# power_supplies.net
KiCad netlist of a schematic drawn in Altium Designer
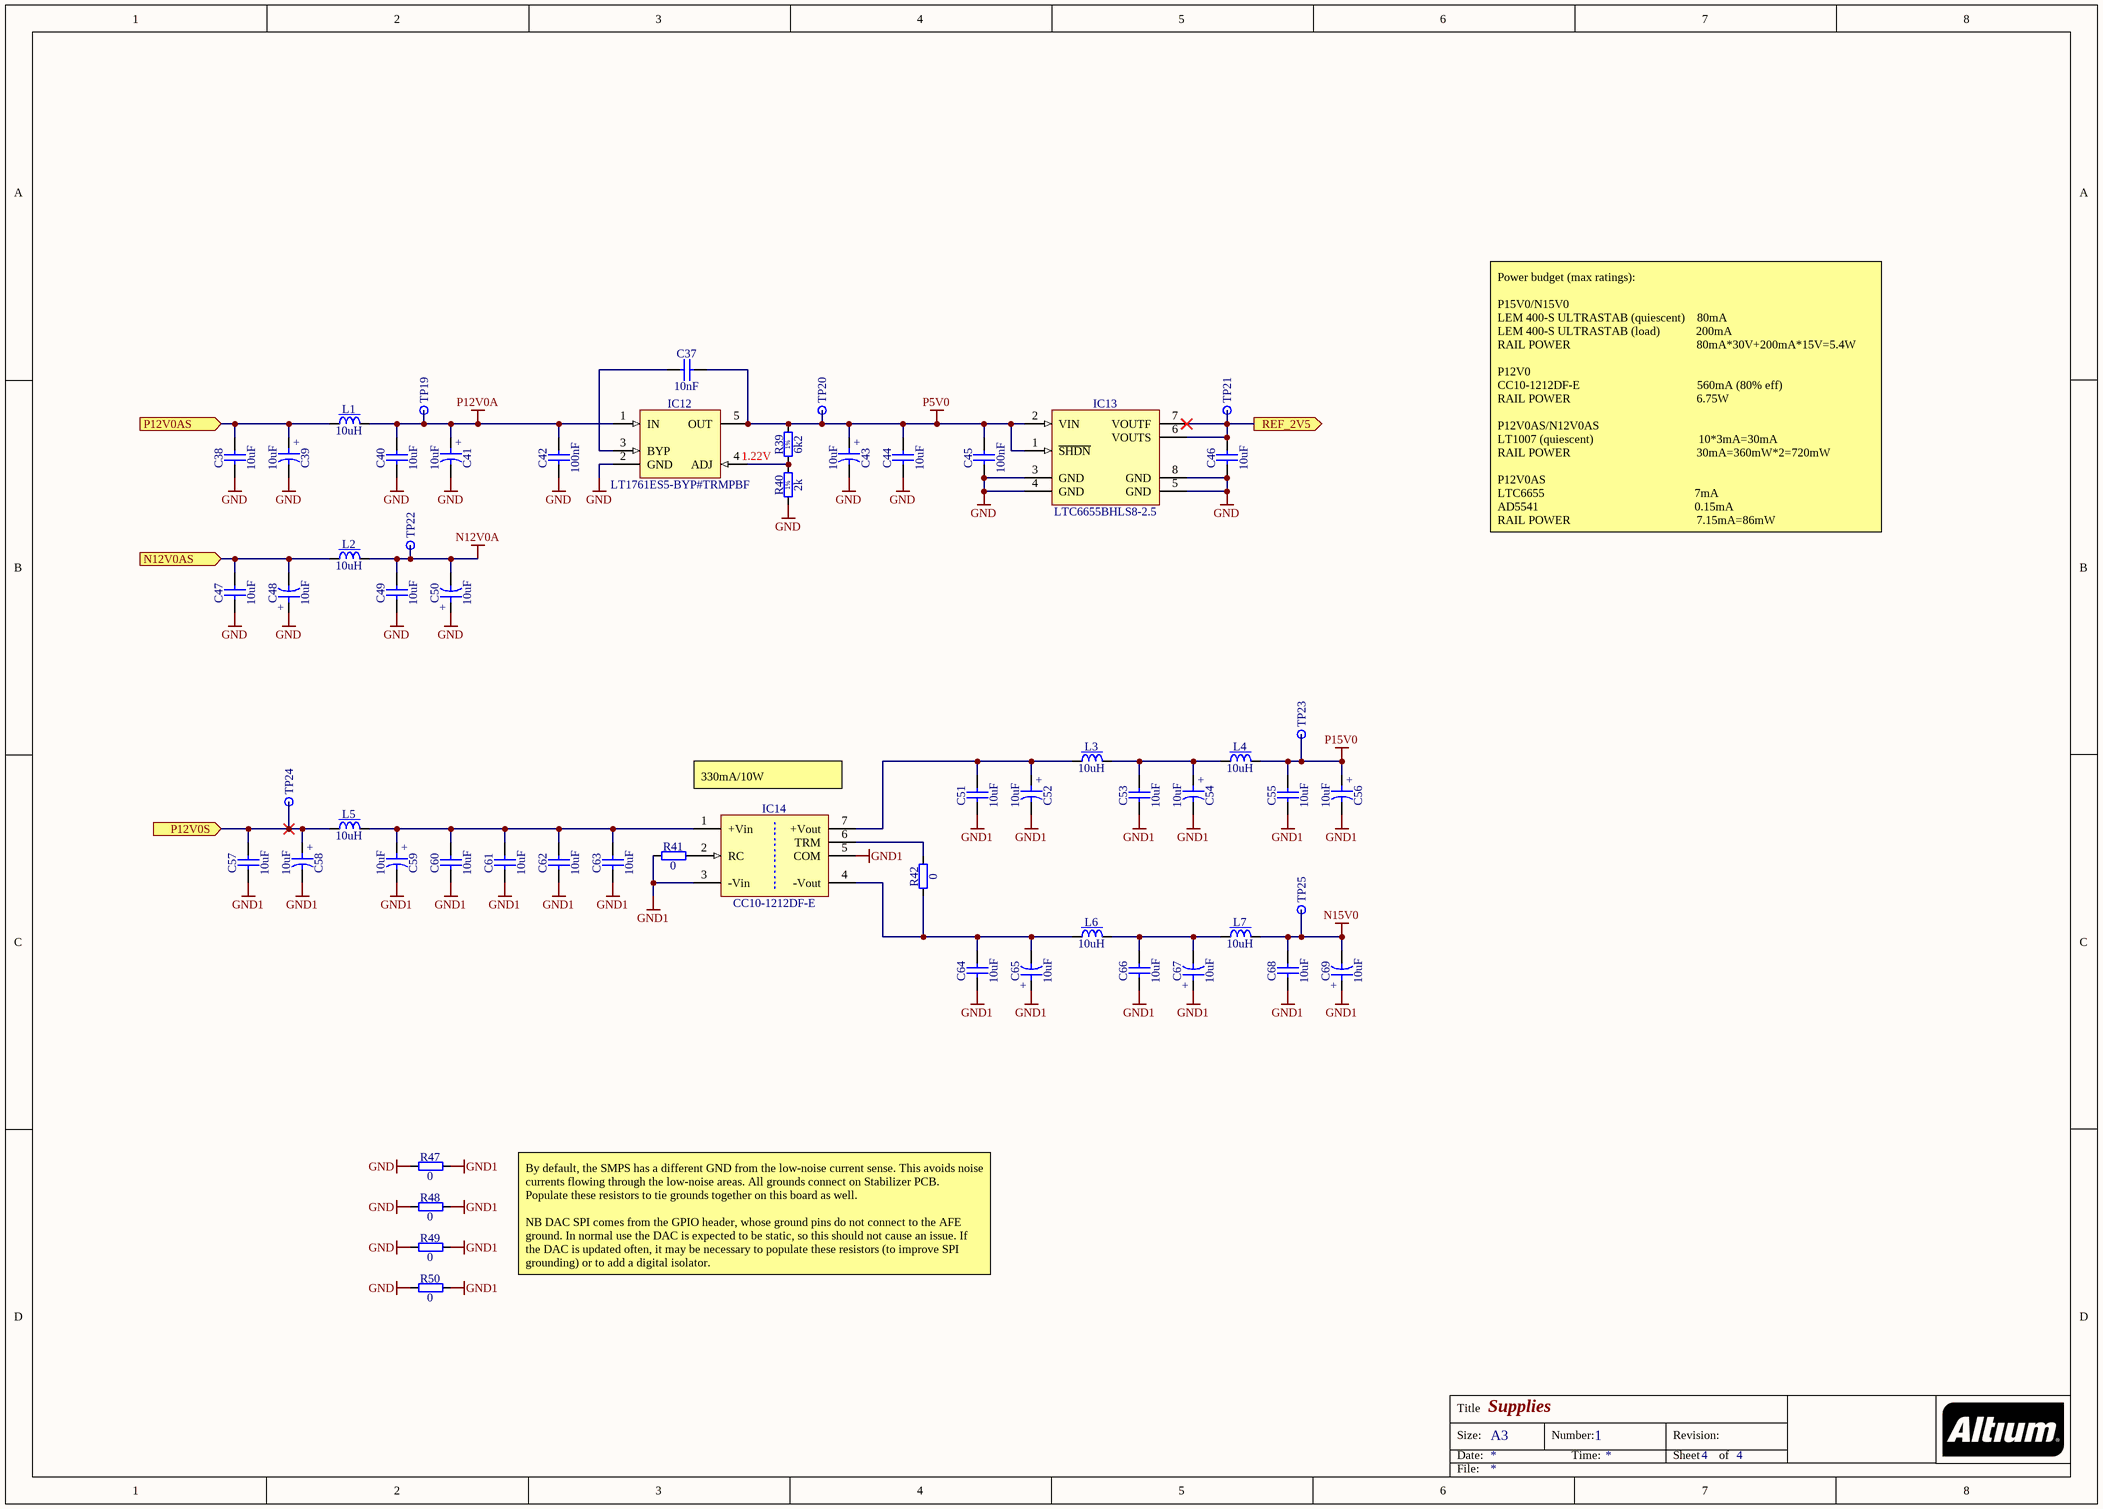
[diagram p0: power_supplies.SchDoc]

(export (version "E")
  (design (tool "Eeschema 10.0.6"))
  (components
    (comp (ref "C37")
      (value "10nF")
      (footprint "CAPC1608X87N")
      (description "Non-polarised capacitor")
      (fields
        (field (name "PART NUMBER") "CC0603_10NF_50V_10%_X7R")
        (field (name "VOLTAGE") "50V")
        (field (name "AUTHOR") "CERN DEM JLC")
      )
      (libsource (lib "Capacitors") (part "Capacitor - non polarized"))
    )
    (comp (ref "C38")
      (value "10uF")
      (footprint "CAPC2012X95N")
      (description "Non-polarised capacitor")
      (fields
        (field (name "PART NUMBER") "CC0805_10UF_25V_10%_X5R")
        (field (name "VOLTAGE") "25V")
        (field (name "AUTHOR") "CERN DEM JLC")
      )
      (libsource (lib "Capacitors") (part "Capacitor - non polarized"))
    )
    (comp (ref "C39")
      (value "10uF")
      (footprint "CAPMP6032X280N")
      (description "Polarised capacitor")
      (fields
        (field (name "PART NUMBER") "CTE6032-28_10UF_25V_10%_LESR0500")
        (field (name "VOLTAGE") "25V")
        (field (name "AUTHOR") "CERN DEM JLC")
      )
      (libsource (lib "Capacitors") (part "Capacitor - polarized"))
    )
    (comp (ref "C40")
      (value "10uF")
      (footprint "CAPC2012X95N")
      (description "Non-polarised capacitor")
      (fields
        (field (name "PART NUMBER") "CC0805_10UF_25V_10%_X5R")
        (field (name "VOLTAGE") "25V")
        (field (name "AUTHOR") "CERN DEM JLC")
      )
      (libsource (lib "Capacitors") (part "Capacitor - non polarized"))
    )
    (comp (ref "C41")
      (value "10uF")
      (footprint "CAPMP6032X280N")
      (description "Polarised capacitor")
      (fields
        (field (name "PART NUMBER") "CTE6032-28_10UF_25V_10%_LESR0500")
        (field (name "VOLTAGE") "25V")
        (field (name "AUTHOR") "CERN DEM JLC")
      )
      (libsource (lib "Capacitors") (part "Capacitor - polarized"))
    )
    (comp (ref "C42")
      (value "100nF")
      (footprint "CAPC1608X87N")
      (description "Non-polarised capacitor")
      (fields
        (field (name "PART NUMBER") "CC0603_100NF_50V_10%_X7R")
        (field (name "VOLTAGE") "50V")
        (field (name "AUTHOR") "CERN DEM JLC")
      )
      (libsource (lib "Capacitors") (part "Capacitor - non polarized"))
    )
    (comp (ref "C43")
      (value "10uF")
      (footprint "CAPMP6032X280N")
      (description "Polarised capacitor")
      (fields
        (field (name "PART NUMBER") "CTE6032-28_10UF_25V_10%_LESR0500")
        (field (name "VOLTAGE") "25V")
        (field (name "AUTHOR") "CERN DEM JLC")
      )
      (libsource (lib "Capacitors") (part "Capacitor - polarized"))
    )
    (comp (ref "C44")
      (value "10uF")
      (footprint "CAPC2012X95N")
      (description "Non-polarised capacitor")
      (fields
        (field (name "PART NUMBER") "CC0805_10UF_25V_10%_X5R")
        (field (name "VOLTAGE") "25V")
        (field (name "AUTHOR") "CERN DEM JLC")
      )
      (libsource (lib "Capacitors") (part "Capacitor - non polarized"))
    )
    (comp (ref "C45")
      (value "100nF")
      (footprint "CAPC1608X87N")
      (description "Non-polarised capacitor")
      (fields
        (field (name "PART NUMBER") "CC0603_100NF_50V_10%_X7R")
        (field (name "VOLTAGE") "50V")
        (field (name "AUTHOR") "CERN DEM JLC")
      )
      (libsource (lib "Capacitors") (part "Capacitor - non polarized"))
    )
    (comp (ref "C46")
      (value "10uF")
      (footprint "CAPC2012X95N")
      (description "Non-polarised capacitor")
      (fields
        (field (name "PART NUMBER") "CC0805_10UF_25V_10%_X5R")
        (field (name "VOLTAGE") "25V")
        (field (name "AUTHOR") "CERN DEM JLC")
      )
      (libsource (lib "Capacitors") (part "Capacitor - non polarized"))
    )
    (comp (ref "C47")
      (value "10uF")
      (footprint "CAPC2012X95N")
      (description "Non-polarised capacitor")
      (fields
        (field (name "PART NUMBER") "CC0805_10UF_25V_10%_X5R")
        (field (name "VOLTAGE") "25V")
        (field (name "AUTHOR") "CERN DEM JLC")
      )
      (libsource (lib "Capacitors") (part "Capacitor - non polarized"))
    )
    (comp (ref "C48")
      (value "10uF")
      (footprint "CAPMP6032X280N")
      (description "Polarised capacitor")
      (fields
        (field (name "PART NUMBER") "CTE6032-28_10UF_25V_10%_LESR0500")
        (field (name "VOLTAGE") "25V")
        (field (name "AUTHOR") "CERN DEM JLC")
      )
      (libsource (lib "Capacitors") (part "Capacitor - polarized"))
    )
    (comp (ref "C49")
      (value "10uF")
      (footprint "CAPC2012X95N")
      (description "Non-polarised capacitor")
      (fields
        (field (name "PART NUMBER") "CC0805_10UF_25V_10%_X5R")
        (field (name "VOLTAGE") "25V")
        (field (name "AUTHOR") "CERN DEM JLC")
      )
      (libsource (lib "Capacitors") (part "Capacitor - non polarized"))
    )
    (comp (ref "C50")
      (value "10uF")
      (footprint "CAPMP6032X280N")
      (description "Polarised capacitor")
      (fields
        (field (name "PART NUMBER") "CTE6032-28_10UF_25V_10%_LESR0500")
        (field (name "VOLTAGE") "25V")
        (field (name "AUTHOR") "CERN DEM JLC")
      )
      (libsource (lib "Capacitors") (part "Capacitor - polarized"))
    )
    (comp (ref "C51")
      (value "10uF")
      (footprint "CAPC2012X95N")
      (description "Non-polarised capacitor")
      (fields
        (field (name "PART NUMBER") "CC0805_10UF_25V_10%_X5R")
        (field (name "VOLTAGE") "25V")
        (field (name "AUTHOR") "CERN DEM JLC")
      )
      (libsource (lib "Capacitors") (part "Capacitor - non polarized"))
    )
    (comp (ref "C52")
      (value "10uF")
      (footprint "CAPMP6032X280N")
      (description "Polarised capacitor")
      (fields
        (field (name "PART NUMBER") "CTE6032-28_10UF_25V_10%_LESR0500")
        (field (name "VOLTAGE") "25V")
        (field (name "AUTHOR") "CERN DEM JLC")
      )
      (libsource (lib "Capacitors") (part "Capacitor - polarized"))
    )
    (comp (ref "C53")
      (value "10uF")
      (footprint "CAPC2012X95N")
      (description "Non-polarised capacitor")
      (fields
        (field (name "PART NUMBER") "CC0805_10UF_25V_10%_X5R")
        (field (name "VOLTAGE") "25V")
        (field (name "AUTHOR") "CERN DEM JLC")
      )
      (libsource (lib "Capacitors") (part "Capacitor - non polarized"))
    )
    (comp (ref "C54")
      (value "10uF")
      (footprint "CAPMP6032X280N")
      (description "Polarised capacitor")
      (fields
        (field (name "PART NUMBER") "CTE6032-28_10UF_25V_10%_LESR0500")
        (field (name "VOLTAGE") "25V")
        (field (name "AUTHOR") "CERN DEM JLC")
      )
      (libsource (lib "Capacitors") (part "Capacitor - polarized"))
    )
    (comp (ref "C55")
      (value "10uF")
      (footprint "CAPC2012X95N")
      (description "Non-polarised capacitor")
      (fields
        (field (name "PART NUMBER") "CC0805_10UF_25V_10%_X5R")
        (field (name "VOLTAGE") "25V")
        (field (name "AUTHOR") "CERN DEM JLC")
      )
      (libsource (lib "Capacitors") (part "Capacitor - non polarized"))
    )
    (comp (ref "C56")
      (value "10uF")
      (footprint "CAPMP6032X280N")
      (description "Polarised capacitor")
      (fields
        (field (name "PART NUMBER") "CTE6032-28_10UF_25V_10%_LESR0500")
        (field (name "VOLTAGE") "25V")
        (field (name "AUTHOR") "CERN DEM JLC")
      )
      (libsource (lib "Capacitors") (part "Capacitor - polarized"))
    )
    (comp (ref "C57")
      (value "10uF")
      (footprint "CAPC2012X95N")
      (description "Non-polarised capacitor")
      (fields
        (field (name "PART NUMBER") "CC0805_10UF_25V_10%_X5R")
        (field (name "VOLTAGE") "25V")
        (field (name "AUTHOR") "CERN DEM JLC")
      )
      (libsource (lib "Capacitors") (part "Capacitor - non polarized"))
    )
    (comp (ref "C58")
      (value "10uF")
      (footprint "CAPMP6032X280N")
      (description "Polarised capacitor")
      (fields
        (field (name "PART NUMBER") "CTE6032-28_10UF_25V_10%_LESR0500")
        (field (name "VOLTAGE") "25V")
        (field (name "AUTHOR") "CERN DEM JLC")
      )
      (libsource (lib "Capacitors") (part "Capacitor - polarized"))
    )
    (comp (ref "C59")
      (value "10uF")
      (footprint "CAPMP6032X280N")
      (description "Polarised capacitor")
      (fields
        (field (name "PART NUMBER") "CTE6032-28_10UF_25V_10%_LESR0500")
        (field (name "VOLTAGE") "25V")
        (field (name "AUTHOR") "CERN DEM JLC")
      )
      (libsource (lib "Capacitors") (part "Capacitor - polarized"))
    )
    (comp (ref "C60")
      (value "10uF")
      (footprint "CAPC2012X95N")
      (description "Non-polarised capacitor")
      (fields
        (field (name "PART NUMBER") "CC0805_10UF_25V_10%_X5R")
        (field (name "VOLTAGE") "25V")
        (field (name "AUTHOR") "CERN DEM JLC")
      )
      (libsource (lib "Capacitors") (part "Capacitor - non polarized"))
    )
    (comp (ref "C61")
      (value "10uF")
      (footprint "CAPC2012X95N")
      (description "Non-polarised capacitor")
      (fields
        (field (name "PART NUMBER") "CC0805_10UF_25V_10%_X5R")
        (field (name "VOLTAGE") "25V")
        (field (name "AUTHOR") "CERN DEM JLC")
      )
      (libsource (lib "Capacitors") (part "Capacitor - non polarized"))
    )
    (comp (ref "C62")
      (value "10uF")
      (footprint "CAPC2012X95N")
      (description "Non-polarised capacitor")
      (fields
        (field (name "PART NUMBER") "CC0805_10UF_25V_10%_X5R")
        (field (name "VOLTAGE") "25V")
        (field (name "AUTHOR") "CERN DEM JLC")
      )
      (libsource (lib "Capacitors") (part "Capacitor - non polarized"))
    )
    (comp (ref "C63")
      (value "10uF")
      (footprint "CAPC2012X95N")
      (description "Non-polarised capacitor")
      (fields
        (field (name "PART NUMBER") "CC0805_10UF_25V_10%_X5R")
        (field (name "VOLTAGE") "25V")
        (field (name "AUTHOR") "CERN DEM JLC")
      )
      (libsource (lib "Capacitors") (part "Capacitor - non polarized"))
    )
    (comp (ref "C64")
      (value "10uF")
      (footprint "CAPC2012X95N")
      (description "Non-polarised capacitor")
      (fields
        (field (name "PART NUMBER") "CC0805_10UF_25V_10%_X5R")
        (field (name "VOLTAGE") "25V")
        (field (name "AUTHOR") "CERN DEM JLC")
      )
      (libsource (lib "Capacitors") (part "Capacitor - non polarized"))
    )
    (comp (ref "C65")
      (value "10uF")
      (footprint "CAPMP6032X280N")
      (description "Polarised capacitor")
      (fields
        (field (name "PART NUMBER") "CTE6032-28_10UF_25V_10%_LESR0500")
        (field (name "VOLTAGE") "25V")
        (field (name "AUTHOR") "CERN DEM JLC")
      )
      (libsource (lib "Capacitors") (part "Capacitor - polarized"))
    )
    (comp (ref "C66")
      (value "10uF")
      (footprint "CAPC2012X95N")
      (description "Non-polarised capacitor")
      (fields
        (field (name "PART NUMBER") "CC0805_10UF_25V_10%_X5R")
        (field (name "VOLTAGE") "25V")
        (field (name "AUTHOR") "CERN DEM JLC")
      )
      (libsource (lib "Capacitors") (part "Capacitor - non polarized"))
    )
    (comp (ref "C67")
      (value "10uF")
      (footprint "CAPMP6032X280N")
      (description "Polarised capacitor")
      (fields
        (field (name "PART NUMBER") "CTE6032-28_10UF_25V_10%_LESR0500")
        (field (name "VOLTAGE") "25V")
        (field (name "AUTHOR") "CERN DEM JLC")
      )
      (libsource (lib "Capacitors") (part "Capacitor - polarized"))
    )
    (comp (ref "C68")
      (value "10uF")
      (footprint "CAPC2012X95N")
      (description "Non-polarised capacitor")
      (fields
        (field (name "PART NUMBER") "CC0805_10UF_25V_10%_X5R")
        (field (name "VOLTAGE") "25V")
        (field (name "AUTHOR") "CERN DEM JLC")
      )
      (libsource (lib "Capacitors") (part "Capacitor - non polarized"))
    )
    (comp (ref "C69")
      (value "10uF")
      (footprint "CAPMP6032X280N")
      (description "Polarised capacitor")
      (fields
        (field (name "PART NUMBER") "CTE6032-28_10UF_25V_10%_LESR0500")
        (field (name "VOLTAGE") "25V")
        (field (name "AUTHOR") "CERN DEM JLC")
      )
      (libsource (lib "Capacitors") (part "Capacitor - polarized"))
    )
    (comp (ref "IC12")
      (value "LT1761ES5-BYP#TRMPBF")
      (footprint "SOT95P280X100-5N")
      (description "100mA, Low Noise, LDO Micropower Adjustable Regulator in SOT-23")
      (fields (field (name "MANUFACTURER") "LINEAR TECHNOLOGY") (field (name "AUTHOR") "CERN DEM MR"))
      (libsource (lib "ICs And Semiconductors") (part "LT1761-BYP"))
    )
    (comp (ref "IC13")
      (value "LTC6655BHLS8-2.5")
      (footprint "LT_LS8")
      (description "2.5V, 0.25ppm Noise, Low Drift Precision Buffered Voltage Reference")
      (fields
        (field (name "MANUFACTURER") "ANALOG DEVICES")
        (field (name "MANUFACTURER PART NUMBER") "LTC6655BHLS8-2.5#PBF")
      )
      (libsource (lib "ICs") (part "LTC6655BHLS8-2.5#PBF"))
    )
    (comp (ref "IC14")
      (value "CC10-1212DF-E")
      (footprint "library-modules:CC10-1212DF-E")
      (description "CONV DC/DC 10W DUAL 12V +-12V PCB")
      (fields (field (name "MANUFACTURER") "TDK-Lambda Americas Inc.") (field (name "AUTHOR") "TPH"))
      (libsource (lib "LIBRARY_SCH") (part "DC/DC_CC10-1212DF-E"))
    )
    (comp (ref "L1")
      (value "10uH")
      (footprint "IND_MURATA-PS_8400")
      (description "Inductor With Core")
      (fields
        (field (name "PART NUMBER") "IND_10UH_10%_MURATA-PS_8400")
        (field (name "POWER") "950mA")
        (field (name "AUTHOR") "CERN DEM JLC")
      )
      (libsource (lib "Inductors & Transformers") (part "Inductor With Magnetic core"))
    )
    (comp (ref "L2")
      (value "10uH")
      (footprint "IND_MURATA-PS_8400")
      (description "Inductor With Core")
      (fields
        (field (name "PART NUMBER") "IND_10UH_10%_MURATA-PS_8400")
        (field (name "POWER") "950mA")
        (field (name "AUTHOR") "CERN DEM JLC")
      )
      (libsource (lib "Inductors & Transformers") (part "Inductor With Magnetic core"))
    )
    (comp (ref "L3")
      (value "10uH")
      (footprint "IND_MURATA-PS_8400")
      (description "Inductor With Core")
      (fields
        (field (name "PART NUMBER") "IND_10UH_10%_MURATA-PS_8400")
        (field (name "POWER") "950mA")
        (field (name "AUTHOR") "CERN DEM JLC")
      )
      (libsource (lib "Inductors & Transformers") (part "Inductor With Magnetic core"))
    )
    (comp (ref "L4")
      (value "10uH")
      (footprint "IND_MURATA-PS_8400")
      (description "Inductor With Core")
      (fields
        (field (name "PART NUMBER") "IND_10UH_10%_MURATA-PS_8400")
        (field (name "POWER") "950mA")
        (field (name "AUTHOR") "CERN DEM JLC")
      )
      (libsource (lib "Inductors & Transformers") (part "Inductor With Magnetic core"))
    )
    (comp (ref "L5")
      (value "10uH")
      (footprint "IND_MURATA-PS_8400")
      (description "Inductor With Core")
      (fields
        (field (name "PART NUMBER") "IND_10UH_10%_MURATA-PS_8400")
        (field (name "POWER") "950mA")
        (field (name "AUTHOR") "CERN DEM JLC")
      )
      (libsource (lib "Inductors & Transformers") (part "Inductor With Magnetic core"))
    )
    (comp (ref "L6")
      (value "10uH")
      (footprint "IND_MURATA-PS_8400")
      (description "Inductor With Core")
      (fields
        (field (name "PART NUMBER") "IND_10UH_10%_MURATA-PS_8400")
        (field (name "POWER") "950mA")
        (field (name "AUTHOR") "CERN DEM JLC")
      )
      (libsource (lib "Inductors & Transformers") (part "Inductor With Magnetic core"))
    )
    (comp (ref "L7")
      (value "10uH")
      (footprint "IND_MURATA-PS_8400")
      (description "Inductor With Core")
      (fields
        (field (name "PART NUMBER") "IND_10UH_10%_MURATA-PS_8400")
        (field (name "POWER") "950mA")
        (field (name "AUTHOR") "CERN DEM JLC")
      )
      (libsource (lib "Inductors & Transformers") (part "Inductor With Magnetic core"))
    )
    (comp (ref "R39")
      (value "6k2")
      (footprint "RESC1608X55N")
      (description "Resistor - 1%")
      (fields
        (field (name "PART NUMBER") "R0603_6K2_1%_0.1W_100PPM")
        (field (name "POWER") "0.1W")
        (field (name "AUTHOR") "CERN DEM JLC")
      )
      (libsource (lib "Resistors") (part "Resistor - 1%"))
    )
    (comp (ref "R40")
      (value "2k")
      (footprint "RESC1608X55N")
      (description "Resistor - 1%")
      (fields
        (field (name "PART NUMBER") "R0603_2K_1%_0.1W_100PPM")
        (field (name "POWER") "0.1W")
        (field (name "AUTHOR") "CERN DEM JLC")
      )
      (libsource (lib "Resistors") (part "Resistor - 1%"))
    )
    (comp (ref "R41")
      (value "0")
      (footprint "RESC1608X55N")
      (description "Resistor")
      (fields
        (field (name "PART NUMBER") "R0603_0R_JUMPER")
        (field (name "MANUFACTURER") "GENERIC")
        (field (name "AUTHOR") "CERN DEM JLC")
      )
      (libsource (lib "Resistors") (part "Resistor"))
    )
    (comp (ref "R42")
      (value "0")
      (footprint "RESC1608X55N")
      (description "Resistor")
      (fields
        (field (name "PART NUMBER") "R0603_0R_JUMPER")
        (field (name "MANUFACTURER") "GENERIC")
        (field (name "AUTHOR") "CERN DEM JLC")
      )
      (libsource (lib "Resistors") (part "Resistor"))
    )
    (comp (ref "R47")
      (value "0")
      (footprint "RESC1608X55N")
      (description "Resistor")
      (fields
        (field (name "PART NUMBER") "R0603_0R_JUMPER")
        (field (name "MANUFACTURER") "GENERIC")
        (field (name "AUTHOR") "CERN DEM JLC")
      )
      (libsource (lib "Resistors") (part "Resistor"))
    )
    (comp (ref "R48")
      (value "0")
      (footprint "RESC1608X55N")
      (description "Resistor")
      (fields
        (field (name "PART NUMBER") "R0603_0R_JUMPER")
        (field (name "MANUFACTURER") "GENERIC")
        (field (name "AUTHOR") "CERN DEM JLC")
      )
      (libsource (lib "Resistors") (part "Resistor"))
    )
    (comp (ref "R49")
      (value "0")
      (footprint "RESC1608X55N")
      (description "Resistor")
      (fields
        (field (name "PART NUMBER") "R0603_0R_JUMPER")
        (field (name "MANUFACTURER") "GENERIC")
        (field (name "AUTHOR") "CERN DEM JLC")
      )
      (libsource (lib "Resistors") (part "Resistor"))
    )
    (comp (ref "R50")
      (value "0")
      (footprint "RESC1608X55N")
      (description "Resistor")
      (fields
        (field (name "PART NUMBER") "R0603_0R_JUMPER")
        (field (name "MANUFACTURER") "GENERIC")
        (field (name "AUTHOR") "CERN DEM JLC")
      )
      (libsource (lib "Resistors") (part "Resistor"))
    )
    (comp (ref "TP19")
      (value "Test Point")
      (footprint "TPS127")
      (fields (field (name "PART NUMBER") "SMD_PAD_1.27X1.27MM") (field (name "AUTHOR") "CERN DEM JLC"))
      (libsource (lib "Eletro-mechanical") (part "Test Point"))
    )
    (comp (ref "TP20")
      (value "Test Point")
      (footprint "TPS127")
      (fields (field (name "PART NUMBER") "SMD_PAD_1.27X1.27MM") (field (name "AUTHOR") "CERN DEM JLC"))
      (libsource (lib "Eletro-mechanical") (part "Test Point"))
    )
    (comp (ref "TP21")
      (value "Test Point")
      (footprint "TPS127")
      (fields (field (name "PART NUMBER") "SMD_PAD_1.27X1.27MM") (field (name "AUTHOR") "CERN DEM JLC"))
      (libsource (lib "Eletro-mechanical") (part "Test Point"))
    )
    (comp (ref "TP22")
      (value "Test Point")
      (footprint "TPS127")
      (fields (field (name "PART NUMBER") "SMD_PAD_1.27X1.27MM") (field (name "AUTHOR") "CERN DEM JLC"))
      (libsource (lib "Eletro-mechanical") (part "Test Point"))
    )
    (comp (ref "TP23")
      (value "Test Point")
      (footprint "TPS127")
      (fields (field (name "PART NUMBER") "SMD_PAD_1.27X1.27MM") (field (name "AUTHOR") "CERN DEM JLC"))
      (libsource (lib "Eletro-mechanical") (part "Test Point"))
    )
    (comp (ref "TP24")
      (value "Test Point")
      (footprint "TPS127")
      (fields (field (name "PART NUMBER") "SMD_PAD_1.27X1.27MM") (field (name "AUTHOR") "CERN DEM JLC"))
      (libsource (lib "Eletro-mechanical") (part "Test Point"))
    )
    (comp (ref "TP25")
      (value "Test Point")
      (footprint "TPS127")
      (fields (field (name "PART NUMBER") "SMD_PAD_1.27X1.27MM") (field (name "AUTHOR") "CERN DEM JLC"))
      (libsource (lib "Eletro-mechanical") (part "Test Point"))
    )
  )
  (nets
    (net (code "1") (name "/N12V0AS") (class "Default")
      (node (ref "C47") (pin "2") (pinfunction "2_2") (pintype "passive"))
      (node (ref "C48") (pin "2") (pinfunction "2_2") (pintype "passive"))
      (node (ref "L2") (pin "1") (pinfunction "1_1") (pintype "passive"))
    )
    (net (code "2") (name "/P12V0AS") (class "Default")
      (node (ref "C38") (pin "2") (pinfunction "2_2") (pintype "passive"))
      (node (ref "C39") (pin "1") (pinfunction "1_1") (pintype "passive"))
      (node (ref "L1") (pin "1") (pinfunction "1_1") (pintype "passive"))
    )
    (net (code "3") (name "/P12V0S") (class "Default")
      (node (ref "C57") (pin "2") (pinfunction "2_2") (pintype "passive"))
      (node (ref "C58") (pin "1") (pinfunction "1_1") (pintype "passive"))
      (node (ref "L5") (pin "1") (pinfunction "1_1") (pintype "passive"))
      (node (ref "TP24") (pin "1") (pinfunction "1_1") (pintype "bidirectional"))
    )
    (net (code "4") (name "/REF_2V5") (class "Default")
      (node (ref "C46") (pin "2") (pinfunction "2_2") (pintype "passive"))
      (node (ref "IC13") (pin "6") (pinfunction "VOUTS_6") (pintype "power_in"))
      (node (ref "IC13") (pin "7") (pinfunction "VOUTF_7") (pintype "power_in"))
      (node (ref "TP21") (pin "1") (pinfunction "1_1") (pintype "bidirectional"))
    )
    (net (code "5") (name "GND") (class "Default")
      (node (ref "C38") (pin "1") (pinfunction "1_1") (pintype "passive"))
      (node (ref "C39") (pin "2") (pinfunction "2_2") (pintype "passive"))
      (node (ref "C40") (pin "1") (pinfunction "1_1") (pintype "passive"))
      (node (ref "C41") (pin "2") (pinfunction "2_2") (pintype "passive"))
      (node (ref "C42") (pin "1") (pinfunction "1_1") (pintype "passive"))
      (node (ref "C43") (pin "2") (pinfunction "2_2") (pintype "passive"))
      (node (ref "C44") (pin "1") (pinfunction "1_1") (pintype "passive"))
      (node (ref "C45") (pin "1") (pinfunction "1_1") (pintype "passive"))
      (node (ref "C46") (pin "1") (pinfunction "1_1") (pintype "passive"))
      (node (ref "C47") (pin "1") (pinfunction "1_1") (pintype "passive"))
      (node (ref "C48") (pin "1") (pinfunction "1_1") (pintype "passive"))
      (node (ref "C49") (pin "1") (pinfunction "1_1") (pintype "passive"))
      (node (ref "C50") (pin "1") (pinfunction "1_1") (pintype "passive"))
      (node (ref "IC12") (pin "2") (pinfunction "GND_2") (pintype "power_in"))
      (node (ref "IC13") (pin "3") (pinfunction "GND_3") (pintype "power_in"))
      (node (ref "IC13") (pin "4") (pinfunction "GND_4") (pintype "power_in"))
      (node (ref "IC13") (pin "5") (pinfunction "GND_5") (pintype "power_in"))
      (node (ref "IC13") (pin "8") (pinfunction "GND_8") (pintype "power_in"))
      (node (ref "R40") (pin "1") (pinfunction "1_1") (pintype "passive"))
      (node (ref "R47") (pin "1") (pinfunction "1_1") (pintype "passive"))
      (node (ref "R48") (pin "1") (pinfunction "1_1") (pintype "passive"))
      (node (ref "R49") (pin "1") (pinfunction "1_1") (pintype "passive"))
      (node (ref "R50") (pin "1") (pinfunction "1_1") (pintype "passive"))
    )
    (net (code "6") (name "GND1") (class "Default")
      (node (ref "C51") (pin "1") (pinfunction "1_1") (pintype "passive"))
      (node (ref "C52") (pin "2") (pinfunction "2_2") (pintype "passive"))
      (node (ref "C53") (pin "1") (pinfunction "1_1") (pintype "passive"))
      (node (ref "C54") (pin "2") (pinfunction "2_2") (pintype "passive"))
      (node (ref "C55") (pin "1") (pinfunction "1_1") (pintype "passive"))
      (node (ref "C56") (pin "2") (pinfunction "2_2") (pintype "passive"))
      (node (ref "C57") (pin "1") (pinfunction "1_1") (pintype "passive"))
      (node (ref "C58") (pin "2") (pinfunction "2_2") (pintype "passive"))
      (node (ref "C59") (pin "2") (pinfunction "2_2") (pintype "passive"))
      (node (ref "C60") (pin "1") (pinfunction "1_1") (pintype "passive"))
      (node (ref "C61") (pin "1") (pinfunction "1_1") (pintype "passive"))
      (node (ref "C62") (pin "1") (pinfunction "1_1") (pintype "passive"))
      (node (ref "C63") (pin "1") (pinfunction "1_1") (pintype "passive"))
      (node (ref "C64") (pin "1") (pinfunction "1_1") (pintype "passive"))
      (node (ref "C65") (pin "1") (pinfunction "1_1") (pintype "passive"))
      (node (ref "C66") (pin "1") (pinfunction "1_1") (pintype "passive"))
      (node (ref "C67") (pin "1") (pinfunction "1_1") (pintype "passive"))
      (node (ref "C68") (pin "1") (pinfunction "1_1") (pintype "passive"))
      (node (ref "C69") (pin "1") (pinfunction "1_1") (pintype "passive"))
      (node (ref "IC14") (pin "3") (pinfunction "-Vin_3") (pintype "power_in"))
      (node (ref "IC14") (pin "5") (pinfunction "COM_5") (pintype "power_in"))
      (node (ref "R41") (pin "1") (pinfunction "1_1") (pintype "passive"))
      (node (ref "R47") (pin "2") (pinfunction "2_2") (pintype "passive"))
      (node (ref "R48") (pin "2") (pinfunction "2_2") (pintype "passive"))
      (node (ref "R49") (pin "2") (pinfunction "2_2") (pintype "passive"))
      (node (ref "R50") (pin "2") (pinfunction "2_2") (pintype "passive"))
    )
    (net (code "7") (name "N12V0A") (class "Default")
      (node (ref "C49") (pin "2") (pinfunction "2_2") (pintype "passive"))
      (node (ref "C50") (pin "2") (pinfunction "2_2") (pintype "passive"))
      (node (ref "L2") (pin "2") (pinfunction "2_2") (pintype "passive"))
      (node (ref "TP22") (pin "1") (pinfunction "1_1") (pintype "bidirectional"))
    )
    (net (code "8") (name "N15V0") (class "Default")
      (node (ref "C68") (pin "2") (pinfunction "2_2") (pintype "passive"))
      (node (ref "C69") (pin "2") (pinfunction "2_2") (pintype "passive"))
      (node (ref "L7") (pin "2") (pinfunction "2_2") (pintype "passive"))
      (node (ref "TP25") (pin "1") (pinfunction "1_1") (pintype "bidirectional"))
    )
    (net (code "9") (name "Net-(C53-Pad2)") (class "Default")
      (node (ref "C53") (pin "2") (pinfunction "2_2") (pintype "passive"))
      (node (ref "C54") (pin "1") (pinfunction "1_1") (pintype "passive"))
      (node (ref "L3") (pin "2") (pinfunction "2_2") (pintype "passive"))
      (node (ref "L4") (pin "1") (pinfunction "1_1") (pintype "passive"))
    )
    (net (code "10") (name "Net-(C66-Pad2)") (class "Default")
      (node (ref "C66") (pin "2") (pinfunction "2_2") (pintype "passive"))
      (node (ref "C67") (pin "2") (pinfunction "2_2") (pintype "passive"))
      (node (ref "L6") (pin "2") (pinfunction "2_2") (pintype "passive"))
      (node (ref "L7") (pin "1") (pinfunction "1_1") (pintype "passive"))
    )
    (net (code "11") (name "Net-(IC12-ADJ)") (class "Default")
      (node (ref "IC12") (pin "4") (pinfunction "ADJ_4") (pintype "input"))
      (node (ref "R39") (pin "1") (pinfunction "1_1") (pintype "passive"))
      (node (ref "R40") (pin "2") (pinfunction "2_2") (pintype "passive"))
    )
    (net (code "12") (name "Net-(IC12-BYP)") (class "Default")
      (node (ref "C37") (pin "1") (pinfunction "1_1") (pintype "passive"))
      (node (ref "IC12") (pin "3") (pinfunction "BYP_3") (pintype "input"))
    )
    (net (code "13") (name "Net-(IC14-+Vin)") (class "Default")
      (node (ref "C59") (pin "1") (pinfunction "1_1") (pintype "passive"))
      (node (ref "C60") (pin "2") (pinfunction "2_2") (pintype "passive"))
      (node (ref "C61") (pin "2") (pinfunction "2_2") (pintype "passive"))
      (node (ref "C62") (pin "2") (pinfunction "2_2") (pintype "passive"))
      (node (ref "C63") (pin "2") (pinfunction "2_2") (pintype "passive"))
      (node (ref "IC14") (pin "1") (pinfunction "+Vin_1") (pintype "power_in"))
      (node (ref "L5") (pin "2") (pinfunction "2_2") (pintype "passive"))
    )
    (net (code "14") (name "Net-(IC14-+Vout)") (class "Default")
      (node (ref "C51") (pin "2") (pinfunction "2_2") (pintype "passive"))
      (node (ref "C52") (pin "1") (pinfunction "1_1") (pintype "passive"))
      (node (ref "IC14") (pin "7") (pinfunction "+Vout_7") (pintype "power_in"))
      (node (ref "L3") (pin "1") (pinfunction "1_1") (pintype "passive"))
    )
    (net (code "15") (name "Net-(IC14--Vout)") (class "Default")
      (node (ref "C64") (pin "2") (pinfunction "2_2") (pintype "passive"))
      (node (ref "C65") (pin "2") (pinfunction "2_2") (pintype "passive"))
      (node (ref "IC14") (pin "4") (pinfunction "-Vout_4") (pintype "power_in"))
      (node (ref "L6") (pin "1") (pinfunction "1_1") (pintype "passive"))
      (node (ref "R42") (pin "1") (pinfunction "1_1") (pintype "passive"))
    )
    (net (code "16") (name "Net-(IC14-RC)") (class "Default")
      (node (ref "IC14") (pin "2") (pinfunction "RC_2") (pintype "input"))
      (node (ref "R41") (pin "2") (pinfunction "2_2") (pintype "passive"))
    )
    (net (code "17") (name "Net-(IC14-TRM)") (class "Default")
      (node (ref "IC14") (pin "6") (pinfunction "TRM_6") (pintype "power_in"))
      (node (ref "R42") (pin "2") (pinfunction "2_2") (pintype "passive"))
    )
    (net (code "18") (name "P5V0") (class "Default")
      (node (ref "C37") (pin "2") (pinfunction "2_2") (pintype "passive"))
      (node (ref "C43") (pin "1") (pinfunction "1_1") (pintype "passive"))
      (node (ref "C44") (pin "2") (pinfunction "2_2") (pintype "passive"))
      (node (ref "C45") (pin "2") (pinfunction "2_2") (pintype "passive"))
      (node (ref "IC12") (pin "5") (pinfunction "OUT_5") (pintype "power_in"))
      (node (ref "IC13") (pin "1") (pinfunction "~{SHDN}_1") (pintype "input"))
      (node (ref "IC13") (pin "2") (pinfunction "VIN_2") (pintype "input"))
      (node (ref "R39") (pin "2") (pinfunction "2_2") (pintype "passive"))
      (node (ref "TP20") (pin "1") (pinfunction "1_1") (pintype "bidirectional"))
    )
    (net (code "19") (name "P12V0A") (class "Default")
      (node (ref "C40") (pin "2") (pinfunction "2_2") (pintype "passive"))
      (node (ref "C41") (pin "1") (pinfunction "1_1") (pintype "passive"))
      (node (ref "C42") (pin "2") (pinfunction "2_2") (pintype "passive"))
      (node (ref "IC12") (pin "1") (pinfunction "IN_1") (pintype "input"))
      (node (ref "L1") (pin "2") (pinfunction "2_2") (pintype "passive"))
      (node (ref "TP19") (pin "1") (pinfunction "1_1") (pintype "bidirectional"))
    )
    (net (code "20") (name "P15V0") (class "Default")
      (node (ref "C55") (pin "2") (pinfunction "2_2") (pintype "passive"))
      (node (ref "C56") (pin "1") (pinfunction "1_1") (pintype "passive"))
      (node (ref "L4") (pin "2") (pinfunction "2_2") (pintype "passive"))
      (node (ref "TP23") (pin "1") (pinfunction "1_1") (pintype "bidirectional"))
    )
  )
)
